# picotouch_synth_flip.net
KiCad netlist of a schematic drawn in EAGLE
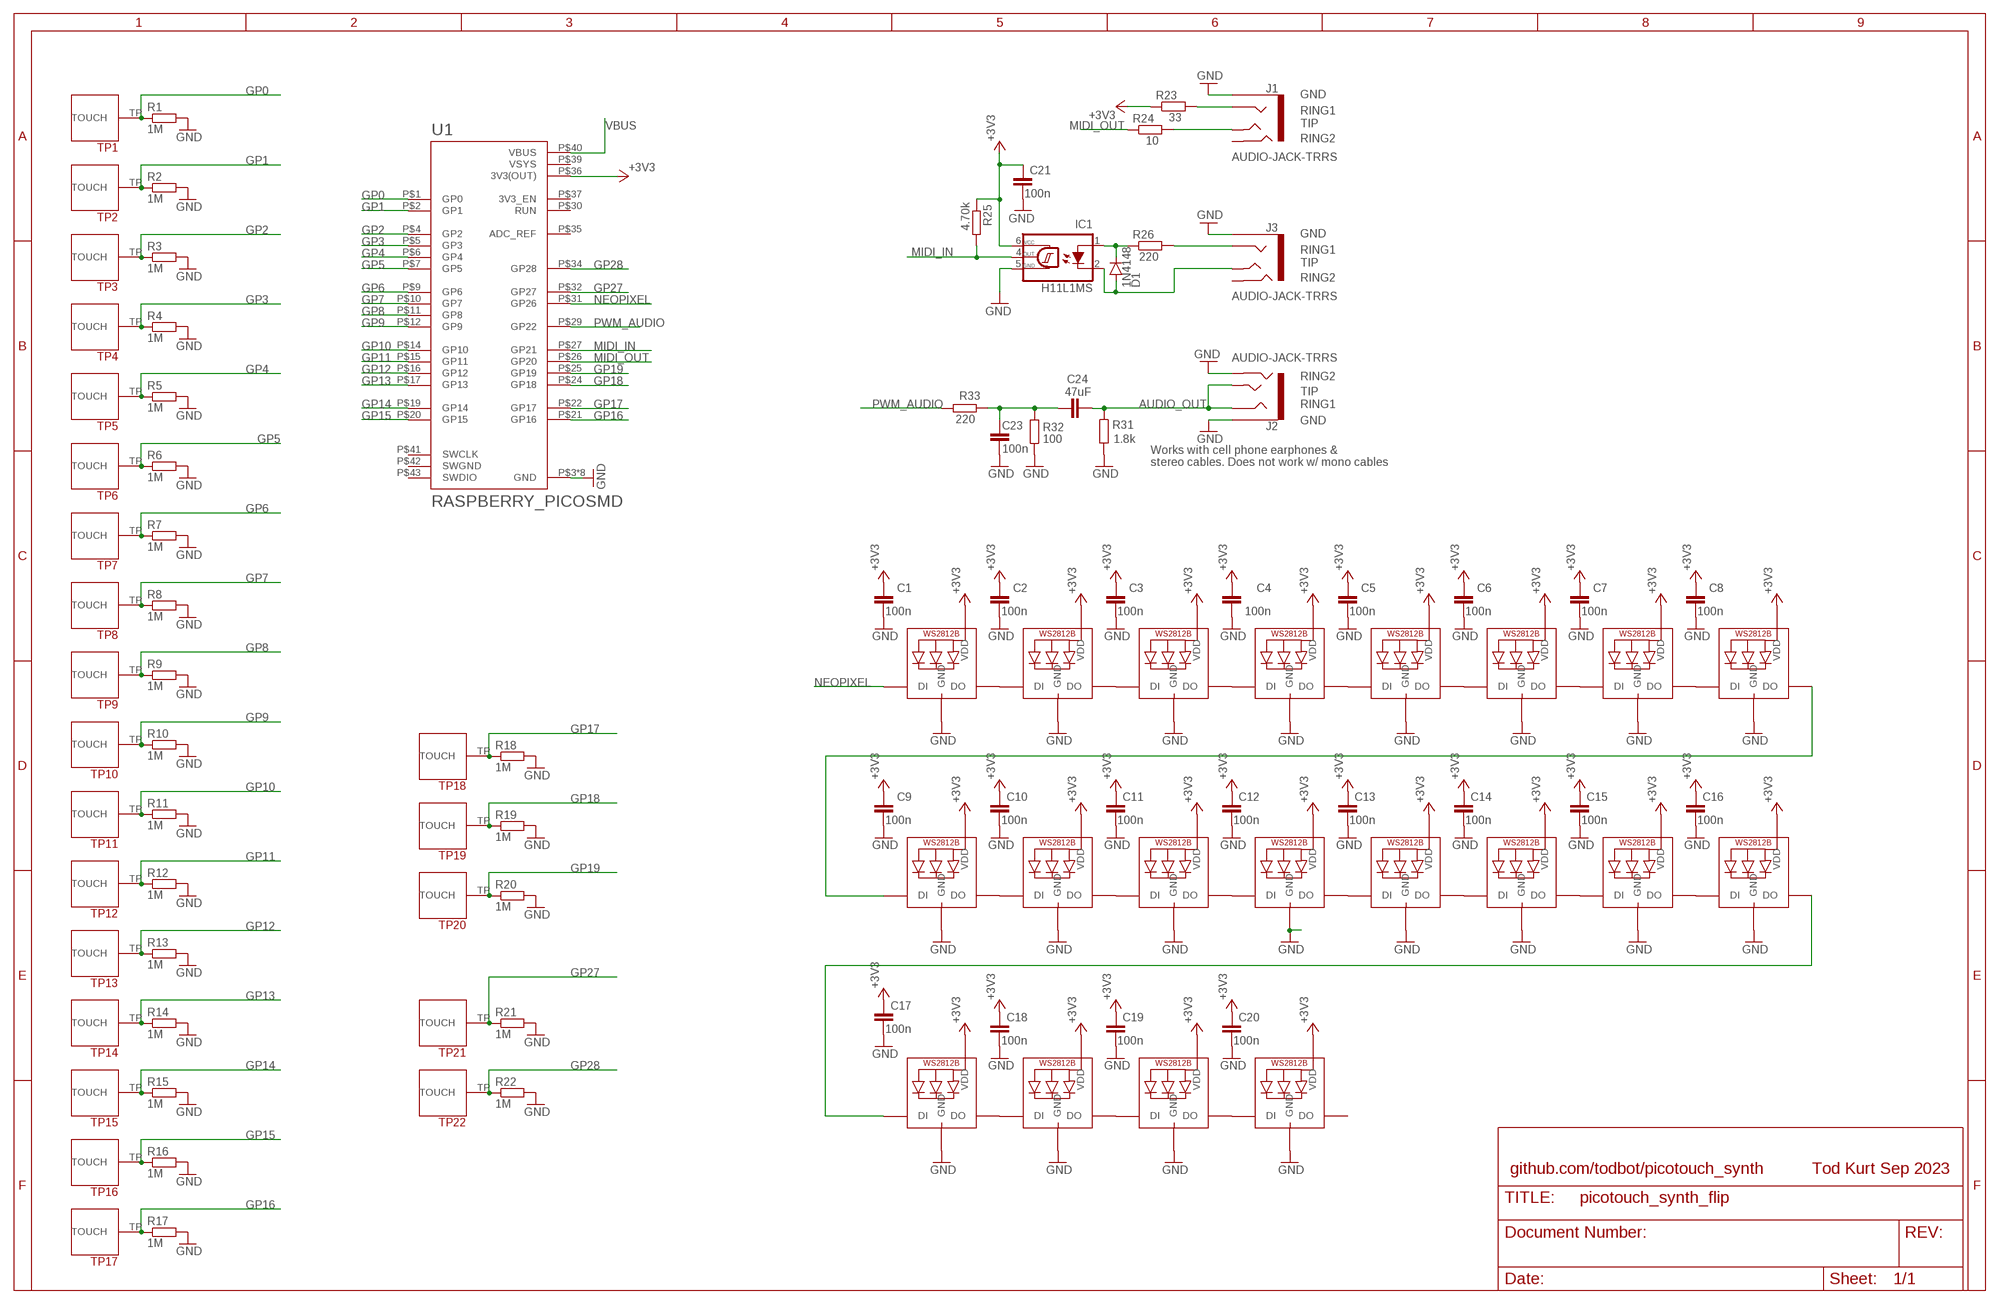
[diagram p0: schematic, sheet 1]

(export (version "E")
  (design (tool "Eeschema 10.0.6"))
  (components
    (comp (ref "C1")
      (value "100n")
      (footprint "eagle-import:C0603")
      (libsource (lib "eagle-import") (part "C-EUC0603"))
    )
    (comp (ref "C2")
      (value "100n")
      (footprint "eagle-import:C0603")
      (libsource (lib "eagle-import") (part "C-EUC0603"))
    )
    (comp (ref "C3")
      (value "100n")
      (footprint "eagle-import:C0603")
      (libsource (lib "eagle-import") (part "C-EUC0603"))
    )
    (comp (ref "C4")
      (value "100n")
      (footprint "eagle-import:C0603")
      (libsource (lib "eagle-import") (part "C-EUC0603"))
    )
    (comp (ref "C5")
      (value "100n")
      (footprint "eagle-import:C0603")
      (libsource (lib "eagle-import") (part "C-EUC0603"))
    )
    (comp (ref "C6")
      (value "100n")
      (footprint "eagle-import:C0603")
      (libsource (lib "eagle-import") (part "C-EUC0603"))
    )
    (comp (ref "C7")
      (value "100n")
      (footprint "eagle-import:C0603")
      (libsource (lib "eagle-import") (part "C-EUC0603"))
    )
    (comp (ref "C8")
      (value "100n")
      (footprint "eagle-import:C0603")
      (libsource (lib "eagle-import") (part "C-EUC0603"))
    )
    (comp (ref "C9")
      (value "100n")
      (footprint "eagle-import:C0603")
      (libsource (lib "eagle-import") (part "C-EUC0603"))
    )
    (comp (ref "C10")
      (value "100n")
      (footprint "eagle-import:C0603")
      (libsource (lib "eagle-import") (part "C-EUC0603"))
    )
    (comp (ref "C11")
      (value "100n")
      (footprint "eagle-import:C0603")
      (libsource (lib "eagle-import") (part "C-EUC0603"))
    )
    (comp (ref "C12")
      (value "100n")
      (footprint "eagle-import:C0603")
      (libsource (lib "eagle-import") (part "C-EUC0603"))
    )
    (comp (ref "C13")
      (value "100n")
      (footprint "eagle-import:C0603")
      (libsource (lib "eagle-import") (part "C-EUC0603"))
    )
    (comp (ref "C14")
      (value "100n")
      (footprint "eagle-import:C0603")
      (libsource (lib "eagle-import") (part "C-EUC0603"))
    )
    (comp (ref "C15")
      (value "100n")
      (footprint "eagle-import:C0603")
      (libsource (lib "eagle-import") (part "C-EUC0603"))
    )
    (comp (ref "C16")
      (value "100n")
      (footprint "eagle-import:C0603")
      (libsource (lib "eagle-import") (part "C-EUC0603"))
    )
    (comp (ref "C17")
      (value "100n")
      (footprint "eagle-import:C0603")
      (libsource (lib "eagle-import") (part "C-EUC0603"))
    )
    (comp (ref "C18")
      (value "100n")
      (footprint "eagle-import:C0603")
      (libsource (lib "eagle-import") (part "C-EUC0603"))
    )
    (comp (ref "C19")
      (value "100n")
      (footprint "eagle-import:C0603")
      (libsource (lib "eagle-import") (part "C-EUC0603"))
    )
    (comp (ref "C20")
      (value "100n")
      (footprint "eagle-import:C0603")
      (libsource (lib "eagle-import") (part "C-EUC0603"))
    )
    (comp (ref "C21")
      (value "100n")
      (footprint "eagle-import:C0603")
      (libsource (lib "eagle-import") (part "C-EUC0603"))
    )
    (comp (ref "C23")
      (value "100n")
      (footprint "eagle-import:C0603")
      (libsource (lib "eagle-import") (part "C-EUC0603"))
    )
    (comp (ref "C24")
      (value "47uF")
      (footprint "eagle-import:C0603")
      (libsource (lib "eagle-import") (part "C-EUC0603"))
    )
    (comp (ref "D1")
      (value "1N4148")
      (footprint "eagle-import:SOD123")
      (libsource (lib "eagle-import") (part "DIODE-SOD123"))
    )
    (comp (ref "IC1")
      (value "H11L1MS")
      (footprint "eagle-import:DIL6-SMD")
      (libsource (lib "eagle-import") (part "H11LMS1"))
    )
    (comp (ref "J1")
      (value "AUDIO-JACK-TRRS")
      (footprint "eagle-import:PJ-320D_SPARKFUN")
      (fields (field (name "MPN") "PJ-320D"))
      (libsource (lib "eagle-import") (part "AUDIO-JACK-TRRS"))
    )
    (comp (ref "J2")
      (value "AUDIO-JACK-TRRS")
      (footprint "eagle-import:PJ-320D_SPARKFUN")
      (fields (field (name "MPN") "PJ-320D") (field (name "LCSC") "C431535"))
      (libsource (lib "eagle-import") (part "AUDIO-JACK-TRRS"))
    )
    (comp (ref "J3")
      (value "AUDIO-JACK-TRRS")
      (footprint "eagle-import:PJ-320D_SPARKFUN")
      (fields (field (name "MPN") "PJ-320D"))
      (libsource (lib "eagle-import") (part "AUDIO-JACK-TRRS"))
    )
    (comp (ref "LED1")
      (value "MICROBUILDER_WS2812B_SK6812E")
      (footprint "eagle-import:MICROBUILDER_NEO3535_REVERSE")
      (libsource (lib "eagle-import") (part "MICROBUILDER_WS2812B_SK6812E"))
    )
    (comp (ref "LED2")
      (value "MICROBUILDER_WS2812B_SK6812E")
      (footprint "eagle-import:MICROBUILDER_NEO3535_REVERSE")
      (libsource (lib "eagle-import") (part "MICROBUILDER_WS2812B_SK6812E"))
    )
    (comp (ref "LED3")
      (value "MICROBUILDER_WS2812B_SK6812E")
      (footprint "eagle-import:MICROBUILDER_NEO3535_REVERSE")
      (libsource (lib "eagle-import") (part "MICROBUILDER_WS2812B_SK6812E"))
    )
    (comp (ref "LED4")
      (value "MICROBUILDER_WS2812B_SK6812E")
      (footprint "eagle-import:MICROBUILDER_NEO3535_REVERSE")
      (libsource (lib "eagle-import") (part "MICROBUILDER_WS2812B_SK6812E"))
    )
    (comp (ref "LED5")
      (value "MICROBUILDER_WS2812B_SK6812E")
      (footprint "eagle-import:MICROBUILDER_NEO3535_REVERSE")
      (libsource (lib "eagle-import") (part "MICROBUILDER_WS2812B_SK6812E"))
    )
    (comp (ref "LED6")
      (value "MICROBUILDER_WS2812B_SK6812E")
      (footprint "eagle-import:MICROBUILDER_NEO3535_REVERSE")
      (libsource (lib "eagle-import") (part "MICROBUILDER_WS2812B_SK6812E"))
    )
    (comp (ref "LED7")
      (value "MICROBUILDER_WS2812B_SK6812E")
      (footprint "eagle-import:MICROBUILDER_NEO3535_REVERSE")
      (libsource (lib "eagle-import") (part "MICROBUILDER_WS2812B_SK6812E"))
    )
    (comp (ref "LED8")
      (value "MICROBUILDER_WS2812B_SK6812E")
      (footprint "eagle-import:MICROBUILDER_NEO3535_REVERSE")
      (libsource (lib "eagle-import") (part "MICROBUILDER_WS2812B_SK6812E"))
    )
    (comp (ref "LED9")
      (value "MICROBUILDER_WS2812B_SK6812E")
      (footprint "eagle-import:MICROBUILDER_NEO3535_REVERSE")
      (libsource (lib "eagle-import") (part "MICROBUILDER_WS2812B_SK6812E"))
    )
    (comp (ref "LED10")
      (value "MICROBUILDER_WS2812B_SK6812E")
      (footprint "eagle-import:MICROBUILDER_NEO3535_REVERSE")
      (libsource (lib "eagle-import") (part "MICROBUILDER_WS2812B_SK6812E"))
    )
    (comp (ref "LED11")
      (value "MICROBUILDER_WS2812B_SK6812E")
      (footprint "eagle-import:MICROBUILDER_NEO3535_REVERSE")
      (libsource (lib "eagle-import") (part "MICROBUILDER_WS2812B_SK6812E"))
    )
    (comp (ref "LED12")
      (value "MICROBUILDER_WS2812B_SK6812E")
      (footprint "eagle-import:MICROBUILDER_NEO3535_REVERSE")
      (libsource (lib "eagle-import") (part "MICROBUILDER_WS2812B_SK6812E"))
    )
    (comp (ref "LED13")
      (value "MICROBUILDER_WS2812B_SK6812E")
      (footprint "eagle-import:MICROBUILDER_NEO3535_REVERSE")
      (libsource (lib "eagle-import") (part "MICROBUILDER_WS2812B_SK6812E"))
    )
    (comp (ref "LED14")
      (value "MICROBUILDER_WS2812B_SK6812E")
      (footprint "eagle-import:MICROBUILDER_NEO3535_REVERSE")
      (libsource (lib "eagle-import") (part "MICROBUILDER_WS2812B_SK6812E"))
    )
    (comp (ref "LED15")
      (value "MICROBUILDER_WS2812B_SK6812E")
      (footprint "eagle-import:MICROBUILDER_NEO3535_REVERSE")
      (libsource (lib "eagle-import") (part "MICROBUILDER_WS2812B_SK6812E"))
    )
    (comp (ref "LED16")
      (value "MICROBUILDER_WS2812B_SK6812E")
      (footprint "eagle-import:MICROBUILDER_NEO3535_REVERSE")
      (libsource (lib "eagle-import") (part "MICROBUILDER_WS2812B_SK6812E"))
    )
    (comp (ref "LED17")
      (value "MICROBUILDER_WS2812B_SK6812E")
      (footprint "eagle-import:MICROBUILDER_NEO3535_REVERSE")
      (libsource (lib "eagle-import") (part "MICROBUILDER_WS2812B_SK6812E"))
    )
    (comp (ref "LED18")
      (value "MICROBUILDER_WS2812B_SK6812E")
      (footprint "eagle-import:MICROBUILDER_NEO3535_REVERSE")
      (libsource (lib "eagle-import") (part "MICROBUILDER_WS2812B_SK6812E"))
    )
    (comp (ref "LED19")
      (value "MICROBUILDER_WS2812B_SK6812E")
      (footprint "eagle-import:MICROBUILDER_NEO3535_REVERSE")
      (libsource (lib "eagle-import") (part "MICROBUILDER_WS2812B_SK6812E"))
    )
    (comp (ref "LED20")
      (value "MICROBUILDER_WS2812B_SK6812E")
      (footprint "eagle-import:MICROBUILDER_NEO3535_REVERSE")
      (libsource (lib "eagle-import") (part "MICROBUILDER_WS2812B_SK6812E"))
    )
    (comp (ref "R1")
      (value "1M")
      (footprint "eagle-import:R0805")
      (libsource (lib "eagle-import") (part "R-EU_R0805"))
    )
    (comp (ref "R2")
      (value "1M")
      (footprint "eagle-import:R0805")
      (libsource (lib "eagle-import") (part "R-EU_R0805"))
    )
    (comp (ref "R3")
      (value "1M")
      (footprint "eagle-import:R0805")
      (libsource (lib "eagle-import") (part "R-EU_R0805"))
    )
    (comp (ref "R4")
      (value "1M")
      (footprint "eagle-import:R0805")
      (libsource (lib "eagle-import") (part "R-EU_R0805"))
    )
    (comp (ref "R5")
      (value "1M")
      (footprint "eagle-import:R0805")
      (libsource (lib "eagle-import") (part "R-EU_R0805"))
    )
    (comp (ref "R6")
      (value "1M")
      (footprint "eagle-import:R0805")
      (libsource (lib "eagle-import") (part "R-EU_R0805"))
    )
    (comp (ref "R7")
      (value "1M")
      (footprint "eagle-import:R0805")
      (libsource (lib "eagle-import") (part "R-EU_R0805"))
    )
    (comp (ref "R8")
      (value "1M")
      (footprint "eagle-import:R0805")
      (libsource (lib "eagle-import") (part "R-EU_R0805"))
    )
    (comp (ref "R9")
      (value "1M")
      (footprint "eagle-import:R0805")
      (libsource (lib "eagle-import") (part "R-EU_R0805"))
    )
    (comp (ref "R10")
      (value "1M")
      (footprint "eagle-import:R0805")
      (libsource (lib "eagle-import") (part "R-EU_R0805"))
    )
    (comp (ref "R11")
      (value "1M")
      (footprint "eagle-import:R0805")
      (libsource (lib "eagle-import") (part "R-EU_R0805"))
    )
    (comp (ref "R12")
      (value "1M")
      (footprint "eagle-import:R0805")
      (libsource (lib "eagle-import") (part "R-EU_R0805"))
    )
    (comp (ref "R13")
      (value "1M")
      (footprint "eagle-import:R0805")
      (libsource (lib "eagle-import") (part "R-EU_R0805"))
    )
    (comp (ref "R14")
      (value "1M")
      (footprint "eagle-import:R0805")
      (libsource (lib "eagle-import") (part "R-EU_R0805"))
    )
    (comp (ref "R15")
      (value "1M")
      (footprint "eagle-import:R0805")
      (libsource (lib "eagle-import") (part "R-EU_R0805"))
    )
    (comp (ref "R16")
      (value "1M")
      (footprint "eagle-import:R0805")
      (libsource (lib "eagle-import") (part "R-EU_R0805"))
    )
    (comp (ref "R17")
      (value "1M")
      (footprint "eagle-import:R0805")
      (libsource (lib "eagle-import") (part "R-EU_R0805"))
    )
    (comp (ref "R18")
      (value "1M")
      (footprint "eagle-import:R0603")
      (libsource (lib "eagle-import") (part "R-EU_R0603"))
    )
    (comp (ref "R19")
      (value "1M")
      (footprint "eagle-import:R0603")
      (libsource (lib "eagle-import") (part "R-EU_R0603"))
    )
    (comp (ref "R20")
      (value "1M")
      (footprint "eagle-import:R0603")
      (libsource (lib "eagle-import") (part "R-EU_R0603"))
    )
    (comp (ref "R21")
      (value "1M")
      (footprint "eagle-import:R0603")
      (libsource (lib "eagle-import") (part "R-EU_R0603"))
    )
    (comp (ref "R22")
      (value "1M")
      (footprint "eagle-import:R0603")
      (libsource (lib "eagle-import") (part "R-EU_R0603"))
    )
    (comp (ref "R23")
      (value "33")
      (footprint "eagle-import:R0603")
      (libsource (lib "eagle-import") (part "R-EU_R0603"))
    )
    (comp (ref "R24")
      (value "10")
      (footprint "eagle-import:R0603")
      (libsource (lib "eagle-import") (part "R-EU_R0603"))
    )
    (comp (ref "R25")
      (value "4.70k")
      (footprint "eagle-import:R0603")
      (libsource (lib "eagle-import") (part "R-EU_R0603"))
    )
    (comp (ref "R26")
      (value "220")
      (footprint "eagle-import:R0603")
      (libsource (lib "eagle-import") (part "R-EU_R0603"))
    )
    (comp (ref "R31")
      (value "1.8k")
      (footprint "eagle-import:R0603")
      (libsource (lib "eagle-import") (part "R-EU_R0603"))
    )
    (comp (ref "R32")
      (value "100")
      (footprint "eagle-import:R0603")
      (libsource (lib "eagle-import") (part "R-EU_R0603"))
    )
    (comp (ref "R33")
      (value "220")
      (footprint "eagle-import:R0603")
      (libsource (lib "eagle-import") (part "R-EU_R0603"))
    )
    (comp (ref "TP1")
      (value "TOUCHPADA")
      (footprint "eagle-import:TOUCHPADA")
      (libsource (lib "eagle-import") (part "TOUCHPADA"))
    )
    (comp (ref "TP2")
      (value "TOUCHPADA")
      (footprint "eagle-import:TOUCHPADA")
      (libsource (lib "eagle-import") (part "TOUCHPADA"))
    )
    (comp (ref "TP3")
      (value "TOUCHPADA")
      (footprint "eagle-import:TOUCHPADA")
      (libsource (lib "eagle-import") (part "TOUCHPADA"))
    )
    (comp (ref "TP4")
      (value "TOUCHPADA")
      (footprint "eagle-import:TOUCHPADA")
      (libsource (lib "eagle-import") (part "TOUCHPADA"))
    )
    (comp (ref "TP5")
      (value "TOUCHPADA")
      (footprint "eagle-import:TOUCHPADA")
      (libsource (lib "eagle-import") (part "TOUCHPADA"))
    )
    (comp (ref "TP6")
      (value "TOUCHPADA")
      (footprint "eagle-import:TOUCHPADA")
      (libsource (lib "eagle-import") (part "TOUCHPADA"))
    )
    (comp (ref "TP7")
      (value "TOUCHPADA")
      (footprint "eagle-import:TOUCHPADA")
      (libsource (lib "eagle-import") (part "TOUCHPADA"))
    )
    (comp (ref "TP8")
      (value "TOUCHPADA")
      (footprint "eagle-import:TOUCHPADA")
      (libsource (lib "eagle-import") (part "TOUCHPADA"))
    )
    (comp (ref "TP9")
      (value "TOUCHPADA")
      (footprint "eagle-import:TOUCHPADA")
      (libsource (lib "eagle-import") (part "TOUCHPADA"))
    )
    (comp (ref "TP10")
      (value "TOUCHPADA")
      (footprint "eagle-import:TOUCHPADA")
      (libsource (lib "eagle-import") (part "TOUCHPADA"))
    )
    (comp (ref "TP11")
      (value "TOUCHPADA")
      (footprint "eagle-import:TOUCHPADA")
      (libsource (lib "eagle-import") (part "TOUCHPADA"))
    )
    (comp (ref "TP12")
      (value "TOUCHPADA")
      (footprint "eagle-import:TOUCHPADA")
      (libsource (lib "eagle-import") (part "TOUCHPADA"))
    )
    (comp (ref "TP13")
      (value "TOUCHPADA")
      (footprint "eagle-import:TOUCHPADA")
      (libsource (lib "eagle-import") (part "TOUCHPADA"))
    )
    (comp (ref "TP14")
      (value "TOUCHPADA")
      (footprint "eagle-import:TOUCHPADA")
      (libsource (lib "eagle-import") (part "TOUCHPADA"))
    )
    (comp (ref "TP15")
      (value "TOUCHPADA")
      (footprint "eagle-import:TOUCHPADA")
      (libsource (lib "eagle-import") (part "TOUCHPADA"))
    )
    (comp (ref "TP16")
      (value "TOUCHPADA")
      (footprint "eagle-import:TOUCHPADA")
      (libsource (lib "eagle-import") (part "TOUCHPADA"))
    )
    (comp (ref "TP17")
      (value "TOUCHPADA")
      (footprint "eagle-import:TOUCHPADA")
      (libsource (lib "eagle-import") (part "TOUCHPADA"))
    )
    (comp (ref "TP18")
      (value "TOUCHPADB")
      (footprint "eagle-import:TOUCHPADB")
      (libsource (lib "eagle-import") (part "TOUCHPADB"))
    )
    (comp (ref "TP19")
      (value "TOUCHPADB")
      (footprint "eagle-import:TOUCHPADB")
      (libsource (lib "eagle-import") (part "TOUCHPADB"))
    )
    (comp (ref "TP20")
      (value "TOUCHPADB")
      (footprint "eagle-import:TOUCHPADB")
      (libsource (lib "eagle-import") (part "TOUCHPADB"))
    )
    (comp (ref "TP21")
      (value "TOUCHPADB")
      (footprint "eagle-import:TOUCHPADB")
      (libsource (lib "eagle-import") (part "TOUCHPADB"))
    )
    (comp (ref "TP22")
      (value "TOUCHPADB")
      (footprint "eagle-import:TOUCHPADB")
      (libsource (lib "eagle-import") (part "TOUCHPADB"))
    )
    (comp (ref "U1")
      (value "RASPBERRY_PICOSMD")
      (footprint "eagle-import:PICO-PKG-SMD")
      (libsource (lib "eagle-import") (part "RASPBERRY_PICOSMD"))
    )
  )
  (nets
    (net (code "1") (name "+3V3") (class "Default")
      (node (ref "C1") (pin "1") (pinfunction "1_1") (pintype "passive"))
      (node (ref "C10") (pin "1") (pinfunction "1_1") (pintype "passive"))
      (node (ref "C11") (pin "1") (pinfunction "1_1") (pintype "passive"))
      (node (ref "C12") (pin "1") (pinfunction "1_1") (pintype "passive"))
      (node (ref "C13") (pin "1") (pinfunction "1_1") (pintype "passive"))
      (node (ref "C14") (pin "1") (pinfunction "1_1") (pintype "passive"))
      (node (ref "C15") (pin "1") (pinfunction "1_1") (pintype "passive"))
      (node (ref "C16") (pin "1") (pinfunction "1_1") (pintype "passive"))
      (node (ref "C17") (pin "1") (pinfunction "1_1") (pintype "passive"))
      (node (ref "C18") (pin "1") (pinfunction "1_1") (pintype "passive"))
      (node (ref "C19") (pin "1") (pinfunction "1_1") (pintype "passive"))
      (node (ref "C2") (pin "1") (pinfunction "1_1") (pintype "passive"))
      (node (ref "C20") (pin "1") (pinfunction "1_1") (pintype "passive"))
      (node (ref "C21") (pin "1") (pinfunction "1_1") (pintype "passive"))
      (node (ref "C3") (pin "1") (pinfunction "1_1") (pintype "passive"))
      (node (ref "C4") (pin "1") (pinfunction "1_1") (pintype "passive"))
      (node (ref "C5") (pin "1") (pinfunction "1_1") (pintype "passive"))
      (node (ref "C6") (pin "1") (pinfunction "1_1") (pintype "passive"))
      (node (ref "C7") (pin "1") (pinfunction "1_1") (pintype "passive"))
      (node (ref "C8") (pin "1") (pinfunction "1_1") (pintype "passive"))
      (node (ref "C9") (pin "1") (pinfunction "1_1") (pintype "passive"))
      (node (ref "IC1") (pin "6") (pinfunction "VCC_6") (pintype "power_in"))
      (node (ref "LED1") (pin "1-VDD") (pinfunction "VDD_1-VDD") (pintype "power_in"))
      (node (ref "LED10") (pin "1-VDD") (pinfunction "VDD_1-VDD") (pintype "power_in"))
      (node (ref "LED11") (pin "1-VDD") (pinfunction "VDD_1-VDD") (pintype "power_in"))
      (node (ref "LED12") (pin "1-VDD") (pinfunction "VDD_1-VDD") (pintype "power_in"))
      (node (ref "LED13") (pin "1-VDD") (pinfunction "VDD_1-VDD") (pintype "power_in"))
      (node (ref "LED14") (pin "1-VDD") (pinfunction "VDD_1-VDD") (pintype "power_in"))
      (node (ref "LED15") (pin "1-VDD") (pinfunction "VDD_1-VDD") (pintype "power_in"))
      (node (ref "LED16") (pin "1-VDD") (pinfunction "VDD_1-VDD") (pintype "power_in"))
      (node (ref "LED17") (pin "1-VDD") (pinfunction "VDD_1-VDD") (pintype "power_in"))
      (node (ref "LED18") (pin "1-VDD") (pinfunction "VDD_1-VDD") (pintype "power_in"))
      (node (ref "LED19") (pin "1-VDD") (pinfunction "VDD_1-VDD") (pintype "power_in"))
      (node (ref "LED2") (pin "1-VDD") (pinfunction "VDD_1-VDD") (pintype "power_in"))
      (node (ref "LED20") (pin "1-VDD") (pinfunction "VDD_1-VDD") (pintype "power_in"))
      (node (ref "LED3") (pin "1-VDD") (pinfunction "VDD_1-VDD") (pintype "power_in"))
      (node (ref "LED4") (pin "1-VDD") (pinfunction "VDD_1-VDD") (pintype "power_in"))
      (node (ref "LED5") (pin "1-VDD") (pinfunction "VDD_1-VDD") (pintype "power_in"))
      (node (ref "LED6") (pin "1-VDD") (pinfunction "VDD_1-VDD") (pintype "power_in"))
      (node (ref "LED7") (pin "1-VDD") (pinfunction "VDD_1-VDD") (pintype "power_in"))
      (node (ref "LED8") (pin "1-VDD") (pinfunction "VDD_1-VDD") (pintype "power_in"))
      (node (ref "LED9") (pin "1-VDD") (pinfunction "VDD_1-VDD") (pintype "power_in"))
      (node (ref "R23") (pin "1") (pinfunction "1_1") (pintype "passive"))
      (node (ref "R25") (pin "1") (pinfunction "1_1") (pintype "passive"))
      (node (ref "U1") (pin "P$36") (pinfunction "3V3(OUT)_P$36") (pintype "power_in"))
    )
    (net (code "2") (name "/AUDIO_OUT") (class "Default")
      (node (ref "C24") (pin "2") (pinfunction "2_2") (pintype "passive"))
      (node (ref "J2") (pin "RING1") (pinfunction "RING1_RING1") (pintype "bidirectional"))
      (node (ref "J2") (pin "TIP") (pinfunction "TIP_TIP") (pintype "bidirectional"))
      (node (ref "R31") (pin "1") (pinfunction "1_1") (pintype "passive"))
    )
    (net (code "3") (name "/GP0") (class "Default")
      (node (ref "R1") (pin "1") (pinfunction "1_1") (pintype "passive"))
      (node (ref "TP1") (pin "TP") (pinfunction "TOUCH_TP") (pintype "bidirectional"))
      (node (ref "U1") (pin "P$1") (pinfunction "GP0_P$1") (pintype "bidirectional"))
    )
    (net (code "4") (name "/GP1") (class "Default")
      (node (ref "R2") (pin "1") (pinfunction "1_1") (pintype "passive"))
      (node (ref "TP2") (pin "TP") (pinfunction "TOUCH_TP") (pintype "bidirectional"))
      (node (ref "U1") (pin "P$2") (pinfunction "GP1_P$2") (pintype "bidirectional"))
    )
    (net (code "5") (name "/GP2") (class "Default")
      (node (ref "R3") (pin "1") (pinfunction "1_1") (pintype "passive"))
      (node (ref "TP3") (pin "TP") (pinfunction "TOUCH_TP") (pintype "bidirectional"))
      (node (ref "U1") (pin "P$4") (pinfunction "GP2_P$4") (pintype "bidirectional"))
    )
    (net (code "6") (name "/GP3") (class "Default")
      (node (ref "R4") (pin "1") (pinfunction "1_1") (pintype "passive"))
      (node (ref "TP4") (pin "TP") (pinfunction "TOUCH_TP") (pintype "bidirectional"))
      (node (ref "U1") (pin "P$5") (pinfunction "GP3_P$5") (pintype "bidirectional"))
    )
    (net (code "7") (name "/GP4") (class "Default")
      (node (ref "R5") (pin "1") (pinfunction "1_1") (pintype "passive"))
      (node (ref "TP5") (pin "TP") (pinfunction "TOUCH_TP") (pintype "bidirectional"))
      (node (ref "U1") (pin "P$6") (pinfunction "GP4_P$6") (pintype "bidirectional"))
    )
    (net (code "8") (name "/GP5") (class "Default")
      (node (ref "R6") (pin "1") (pinfunction "1_1") (pintype "passive"))
      (node (ref "TP6") (pin "TP") (pinfunction "TOUCH_TP") (pintype "bidirectional"))
      (node (ref "U1") (pin "P$7") (pinfunction "GP5_P$7") (pintype "bidirectional"))
    )
    (net (code "9") (name "/GP6") (class "Default")
      (node (ref "R7") (pin "1") (pinfunction "1_1") (pintype "passive"))
      (node (ref "TP7") (pin "TP") (pinfunction "TOUCH_TP") (pintype "bidirectional"))
      (node (ref "U1") (pin "P$9") (pinfunction "GP6_P$9") (pintype "bidirectional"))
    )
    (net (code "10") (name "/GP7") (class "Default")
      (node (ref "R8") (pin "1") (pinfunction "1_1") (pintype "passive"))
      (node (ref "TP8") (pin "TP") (pinfunction "TOUCH_TP") (pintype "bidirectional"))
      (node (ref "U1") (pin "P$10") (pinfunction "GP7_P$10") (pintype "bidirectional"))
    )
    (net (code "11") (name "/GP8") (class "Default")
      (node (ref "R9") (pin "1") (pinfunction "1_1") (pintype "passive"))
      (node (ref "TP9") (pin "TP") (pinfunction "TOUCH_TP") (pintype "bidirectional"))
      (node (ref "U1") (pin "P$11") (pinfunction "GP8_P$11") (pintype "bidirectional"))
    )
    (net (code "12") (name "/GP9") (class "Default")
      (node (ref "R10") (pin "1") (pinfunction "1_1") (pintype "passive"))
      (node (ref "TP10") (pin "TP") (pinfunction "TOUCH_TP") (pintype "bidirectional"))
      (node (ref "U1") (pin "P$12") (pinfunction "GP9_P$12") (pintype "bidirectional"))
    )
    (net (code "13") (name "/GP10") (class "Default")
      (node (ref "R11") (pin "1") (pinfunction "1_1") (pintype "passive"))
      (node (ref "TP11") (pin "TP") (pinfunction "TOUCH_TP") (pintype "bidirectional"))
      (node (ref "U1") (pin "P$14") (pinfunction "GP10_P$14") (pintype "bidirectional"))
    )
    (net (code "14") (name "/GP11") (class "Default")
      (node (ref "R12") (pin "1") (pinfunction "1_1") (pintype "passive"))
      (node (ref "TP12") (pin "TP") (pinfunction "TOUCH_TP") (pintype "bidirectional"))
      (node (ref "U1") (pin "P$15") (pinfunction "GP11_P$15") (pintype "bidirectional"))
    )
    (net (code "15") (name "/GP12") (class "Default")
      (node (ref "R13") (pin "1") (pinfunction "1_1") (pintype "passive"))
      (node (ref "TP13") (pin "TP") (pinfunction "TOUCH_TP") (pintype "bidirectional"))
      (node (ref "U1") (pin "P$16") (pinfunction "GP12_P$16") (pintype "bidirectional"))
    )
    (net (code "16") (name "/GP13") (class "Default")
      (node (ref "R14") (pin "1") (pinfunction "1_1") (pintype "passive"))
      (node (ref "TP14") (pin "TP") (pinfunction "TOUCH_TP") (pintype "bidirectional"))
      (node (ref "U1") (pin "P$17") (pinfunction "GP13_P$17") (pintype "bidirectional"))
    )
    (net (code "17") (name "/GP14") (class "Default")
      (node (ref "R15") (pin "1") (pinfunction "1_1") (pintype "passive"))
      (node (ref "TP15") (pin "TP") (pinfunction "TOUCH_TP") (pintype "bidirectional"))
      (node (ref "U1") (pin "P$19") (pinfunction "GP14_P$19") (pintype "bidirectional"))
    )
    (net (code "18") (name "/GP15") (class "Default")
      (node (ref "R16") (pin "1") (pinfunction "1_1") (pintype "passive"))
      (node (ref "TP16") (pin "TP") (pinfunction "TOUCH_TP") (pintype "bidirectional"))
      (node (ref "U1") (pin "P$20") (pinfunction "GP15_P$20") (pintype "bidirectional"))
    )
    (net (code "19") (name "/GP16") (class "Default")
      (node (ref "R17") (pin "1") (pinfunction "1_1") (pintype "passive"))
      (node (ref "TP17") (pin "TP") (pinfunction "TOUCH_TP") (pintype "bidirectional"))
      (node (ref "U1") (pin "P$21") (pinfunction "GP16_P$21") (pintype "bidirectional"))
    )
    (net (code "20") (name "/GP17") (class "Default")
      (node (ref "R18") (pin "1") (pinfunction "1_1") (pintype "passive"))
      (node (ref "TP18") (pin "TP") (pinfunction "TOUCH_TP") (pintype "bidirectional"))
      (node (ref "U1") (pin "P$22") (pinfunction "GP17_P$22") (pintype "bidirectional"))
    )
    (net (code "21") (name "/GP18") (class "Default")
      (node (ref "R19") (pin "1") (pinfunction "1_1") (pintype "passive"))
      (node (ref "TP19") (pin "TP") (pinfunction "TOUCH_TP") (pintype "bidirectional"))
      (node (ref "U1") (pin "P$24") (pinfunction "GP18_P$24") (pintype "bidirectional"))
    )
    (net (code "22") (name "/GP19") (class "Default")
      (node (ref "R20") (pin "1") (pinfunction "1_1") (pintype "passive"))
      (node (ref "TP20") (pin "TP") (pinfunction "TOUCH_TP") (pintype "bidirectional"))
      (node (ref "U1") (pin "P$25") (pinfunction "GP19_P$25") (pintype "bidirectional"))
    )
    (net (code "23") (name "/GP27") (class "Default")
      (node (ref "R21") (pin "1") (pinfunction "1_1") (pintype "passive"))
      (node (ref "TP21") (pin "TP") (pinfunction "TOUCH_TP") (pintype "bidirectional"))
      (node (ref "U1") (pin "P$32") (pinfunction "GP27_P$32") (pintype "bidirectional"))
    )
    (net (code "24") (name "/GP28") (class "Default")
      (node (ref "R22") (pin "1") (pinfunction "1_1") (pintype "passive"))
      (node (ref "TP22") (pin "TP") (pinfunction "TOUCH_TP") (pintype "bidirectional"))
      (node (ref "U1") (pin "P$34") (pinfunction "GP28_P$34") (pintype "bidirectional"))
    )
    (net (code "25") (name "/MIDI_IN") (class "Default")
      (node (ref "IC1") (pin "4") (pinfunction "OUT_4") (pintype "output"))
      (node (ref "R25") (pin "2") (pinfunction "2_2") (pintype "passive"))
      (node (ref "U1") (pin "P$27") (pinfunction "GP21_P$27") (pintype "bidirectional"))
    )
    (net (code "26") (name "/MIDI_OUT") (class "Default")
      (node (ref "R24") (pin "1") (pinfunction "1_1") (pintype "passive"))
      (node (ref "U1") (pin "P$26") (pinfunction "GP20_P$26") (pintype "bidirectional"))
    )
    (net (code "27") (name "/NEOPIXEL") (class "Default")
      (node (ref "LED1") (pin "4-DIN") (pinfunction "DI_4-DIN") (pintype "input"))
      (node (ref "U1") (pin "P$31") (pinfunction "GP26_P$31") (pintype "bidirectional"))
    )
    (net (code "28") (name "/PWM_AUDIO") (class "Default")
      (node (ref "R33") (pin "2") (pinfunction "2_2") (pintype "passive"))
      (node (ref "U1") (pin "P$29") (pinfunction "GP22_P$29") (pintype "bidirectional"))
    )
    (net (code "29") (name "/SWGND") (class "Default")
      (node (ref "U1") (pin "P$42") (pinfunction "SWGND_P$42") (pintype "power_in"))
    )
    (net (code "30") (name "/VBUS") (class "Default")
      (node (ref "U1") (pin "P$40") (pinfunction "VBUS_P$40") (pintype "power_in"))
    )
    (net (code "31") (name "/VSYS") (class "Default")
      (node (ref "U1") (pin "P$39") (pinfunction "VSYS_P$39") (pintype "power_in"))
    )
    (net (code "32") (name "GND") (class "Default")
      (node (ref "C1") (pin "2") (pinfunction "2_2") (pintype "passive"))
      (node (ref "C10") (pin "2") (pinfunction "2_2") (pintype "passive"))
      (node (ref "C11") (pin "2") (pinfunction "2_2") (pintype "passive"))
      (node (ref "C12") (pin "2") (pinfunction "2_2") (pintype "passive"))
      (node (ref "C13") (pin "2") (pinfunction "2_2") (pintype "passive"))
      (node (ref "C14") (pin "2") (pinfunction "2_2") (pintype "passive"))
      (node (ref "C15") (pin "2") (pinfunction "2_2") (pintype "passive"))
      (node (ref "C16") (pin "2") (pinfunction "2_2") (pintype "passive"))
      (node (ref "C17") (pin "2") (pinfunction "2_2") (pintype "passive"))
      (node (ref "C18") (pin "2") (pinfunction "2_2") (pintype "passive"))
      (node (ref "C19") (pin "2") (pinfunction "2_2") (pintype "passive"))
      (node (ref "C2") (pin "2") (pinfunction "2_2") (pintype "passive"))
      (node (ref "C20") (pin "2") (pinfunction "2_2") (pintype "passive"))
      (node (ref "C21") (pin "2") (pinfunction "2_2") (pintype "passive"))
      (node (ref "C23") (pin "2") (pinfunction "2_2") (pintype "passive"))
      (node (ref "C3") (pin "2") (pinfunction "2_2") (pintype "passive"))
      (node (ref "C4") (pin "2") (pinfunction "2_2") (pintype "passive"))
      (node (ref "C5") (pin "2") (pinfunction "2_2") (pintype "passive"))
      (node (ref "C6") (pin "2") (pinfunction "2_2") (pintype "passive"))
      (node (ref "C7") (pin "2") (pinfunction "2_2") (pintype "passive"))
      (node (ref "C8") (pin "2") (pinfunction "2_2") (pintype "passive"))
      (node (ref "C9") (pin "2") (pinfunction "2_2") (pintype "passive"))
      (node (ref "IC1") (pin "5") (pinfunction "GND_5") (pintype "power_in"))
      (node (ref "J1") (pin "EARTH") (pinfunction "EARTH_EARTH") (pintype "bidirectional"))
      (node (ref "J2") (pin "EARTH") (pinfunction "EARTH_EARTH") (pintype "bidirectional"))
      (node (ref "J2") (pin "RING2") (pinfunction "RING2_RING2") (pintype "bidirectional"))
      (node (ref "J3") (pin "EARTH") (pinfunction "EARTH_EARTH") (pintype "bidirectional"))
      (node (ref "LED1") (pin "3-GND") (pinfunction "GND_3-GND") (pintype "power_in"))
      (node (ref "LED10") (pin "3-GND") (pinfunction "GND_3-GND") (pintype "power_in"))
      (node (ref "LED11") (pin "3-GND") (pinfunction "GND_3-GND") (pintype "power_in"))
      (node (ref "LED12") (pin "3-GND") (pinfunction "GND_3-GND") (pintype "power_in"))
      (node (ref "LED13") (pin "3-GND") (pinfunction "GND_3-GND") (pintype "power_in"))
      (node (ref "LED14") (pin "3-GND") (pinfunction "GND_3-GND") (pintype "power_in"))
      (node (ref "LED15") (pin "3-GND") (pinfunction "GND_3-GND") (pintype "power_in"))
      (node (ref "LED16") (pin "3-GND") (pinfunction "GND_3-GND") (pintype "power_in"))
      (node (ref "LED17") (pin "3-GND") (pinfunction "GND_3-GND") (pintype "power_in"))
      (node (ref "LED18") (pin "3-GND") (pinfunction "GND_3-GND") (pintype "power_in"))
      (node (ref "LED19") (pin "3-GND") (pinfunction "GND_3-GND") (pintype "power_in"))
      (node (ref "LED2") (pin "3-GND") (pinfunction "GND_3-GND") (pintype "power_in"))
      (node (ref "LED20") (pin "3-GND") (pinfunction "GND_3-GND") (pintype "power_in"))
      (node (ref "LED3") (pin "3-GND") (pinfunction "GND_3-GND") (pintype "power_in"))
      (node (ref "LED4") (pin "3-GND") (pinfunction "GND_3-GND") (pintype "power_in"))
      (node (ref "LED5") (pin "3-GND") (pinfunction "GND_3-GND") (pintype "power_in"))
      (node (ref "LED6") (pin "3-GND") (pinfunction "GND_3-GND") (pintype "power_in"))
      (node (ref "LED7") (pin "3-GND") (pinfunction "GND_3-GND") (pintype "power_in"))
      (node (ref "LED8") (pin "3-GND") (pinfunction "GND_3-GND") (pintype "power_in"))
      (node (ref "LED9") (pin "3-GND") (pinfunction "GND_3-GND") (pintype "power_in"))
      (node (ref "R1") (pin "2") (pinfunction "2_2") (pintype "passive"))
      (node (ref "R10") (pin "2") (pinfunction "2_2") (pintype "passive"))
      (node (ref "R11") (pin "2") (pinfunction "2_2") (pintype "passive"))
      (node (ref "R12") (pin "2") (pinfunction "2_2") (pintype "passive"))
      (node (ref "R13") (pin "2") (pinfunction "2_2") (pintype "passive"))
      (node (ref "R14") (pin "2") (pinfunction "2_2") (pintype "passive"))
      (node (ref "R15") (pin "2") (pinfunction "2_2") (pintype "passive"))
      (node (ref "R16") (pin "2") (pinfunction "2_2") (pintype "passive"))
      (node (ref "R17") (pin "2") (pinfunction "2_2") (pintype "passive"))
      (node (ref "R18") (pin "2") (pinfunction "2_2") (pintype "passive"))
      (node (ref "R19") (pin "2") (pinfunction "2_2") (pintype "passive"))
      (node (ref "R2") (pin "2") (pinfunction "2_2") (pintype "passive"))
      (node (ref "R20") (pin "2") (pinfunction "2_2") (pintype "passive"))
      (node (ref "R21") (pin "2") (pinfunction "2_2") (pintype "passive"))
      (node (ref "R22") (pin "2") (pinfunction "2_2") (pintype "passive"))
      (node (ref "R3") (pin "2") (pinfunction "2_2") (pintype "passive"))
      (node (ref "R31") (pin "2") (pinfunction "2_2") (pintype "passive"))
      (node (ref "R32") (pin "1") (pinfunction "1_1") (pintype "passive"))
      (node (ref "R4") (pin "2") (pinfunction "2_2") (pintype "passive"))
      (node (ref "R5") (pin "2") (pinfunction "2_2") (pintype "passive"))
      (node (ref "R6") (pin "2") (pinfunction "2_2") (pintype "passive"))
      (node (ref "R7") (pin "2") (pinfunction "2_2") (pintype "passive"))
      (node (ref "R8") (pin "2") (pinfunction "2_2") (pintype "passive"))
      (node (ref "R9") (pin "2") (pinfunction "2_2") (pintype "passive"))
      (node (ref "U1") (pin "P$13") (pinfunction "GND_P$13") (pintype "power_in"))
      (node (ref "U1") (pin "P$18") (pinfunction "GND_P$18") (pintype "power_in"))
      (node (ref "U1") (pin "P$23") (pinfunction "GND_P$23") (pintype "power_in"))
      (node (ref "U1") (pin "P$28") (pinfunction "GND_P$28") (pintype "power_in"))
      (node (ref "U1") (pin "P$3") (pinfunction "GND_P$3") (pintype "power_in"))
      (node (ref "U1") (pin "P$33") (pinfunction "GND_P$33") (pintype "power_in"))
      (node (ref "U1") (pin "P$38") (pinfunction "GND_P$38") (pintype "power_in"))
      (node (ref "U1") (pin "P$8") (pinfunction "GND_P$8") (pintype "power_in"))
    )
    (net (code "33") (name "Net-(C23-Pad1)") (class "Default")
      (node (ref "C23") (pin "1") (pinfunction "1_1") (pintype "passive"))
      (node (ref "C24") (pin "1") (pinfunction "1_1") (pintype "passive"))
      (node (ref "R32") (pin "2") (pinfunction "2_2") (pintype "passive"))
      (node (ref "R33") (pin "1") (pinfunction "1_1") (pintype "passive"))
    )
    (net (code "34") (name "Net-(IC1-A)") (class "Default")
      (node (ref "D1") (pin "C") (pinfunction "C_C") (pintype "passive"))
      (node (ref "IC1") (pin "1") (pinfunction "A_1") (pintype "passive"))
      (node (ref "R26") (pin "1") (pinfunction "1_1") (pintype "passive"))
    )
    (net (code "35") (name "Net-(IC1-C)") (class "Default")
      (node (ref "D1") (pin "A") (pinfunction "A_A") (pintype "passive"))
      (node (ref "IC1") (pin "2") (pinfunction "C_2") (pintype "passive"))
      (node (ref "J3") (pin "TIP") (pinfunction "TIP_TIP") (pintype "bidirectional"))
    )
    (net (code "36") (name "Net-(J1-PadRING1)") (class "Default")
      (node (ref "J1") (pin "RING1") (pinfunction "RING1_RING1") (pintype "bidirectional"))
      (node (ref "R23") (pin "2") (pinfunction "2_2") (pintype "passive"))
    )
    (net (code "37") (name "Net-(J1-PadTIP)") (class "Default")
      (node (ref "J1") (pin "TIP") (pinfunction "TIP_TIP") (pintype "bidirectional"))
      (node (ref "R24") (pin "2") (pinfunction "2_2") (pintype "passive"))
    )
    (net (code "38") (name "Net-(J3-PadRING1)") (class "Default")
      (node (ref "J3") (pin "RING1") (pinfunction "RING1_RING1") (pintype "bidirectional"))
      (node (ref "R26") (pin "2") (pinfunction "2_2") (pintype "passive"))
    )
    (net (code "39") (name "Net-(LED1-DO)") (class "Default")
      (node (ref "LED1") (pin "2-DOUT") (pinfunction "DO_2-DOUT") (pintype "output"))
      (node (ref "LED2") (pin "4-DIN") (pinfunction "DI_4-DIN") (pintype "input"))
    )
    (net (code "40") (name "Net-(LED2-DO)") (class "Default")
      (node (ref "LED2") (pin "2-DOUT") (pinfunction "DO_2-DOUT") (pintype "output"))
      (node (ref "LED3") (pin "4-DIN") (pinfunction "DI_4-DIN") (pintype "input"))
    )
    (net (code "41") (name "Net-(LED3-DO)") (class "Default")
      (node (ref "LED3") (pin "2-DOUT") (pinfunction "DO_2-DOUT") (pintype "output"))
      (node (ref "LED4") (pin "4-DIN") (pinfunction "DI_4-DIN") (pintype "input"))
    )
    (net (code "42") (name "Net-(LED4-DO)") (class "Default")
      (node (ref "LED4") (pin "2-DOUT") (pinfunction "DO_2-DOUT") (pintype "output"))
      (node (ref "LED5") (pin "4-DIN") (pinfunction "DI_4-DIN") (pintype "input"))
    )
    (net (code "43") (name "Net-(LED5-DO)") (class "Default")
      (node (ref "LED5") (pin "2-DOUT") (pinfunction "DO_2-DOUT") (pintype "output"))
      (node (ref "LED6") (pin "4-DIN") (pinfunction "DI_4-DIN") (pintype "input"))
    )
    (net (code "44") (name "Net-(LED6-DO)") (class "Default")
      (node (ref "LED6") (pin "2-DOUT") (pinfunction "DO_2-DOUT") (pintype "output"))
      (node (ref "LED7") (pin "4-DIN") (pinfunction "DI_4-DIN") (pintype "input"))
    )
    (net (code "45") (name "Net-(LED7-DO)") (class "Default")
      (node (ref "LED7") (pin "2-DOUT") (pinfunction "DO_2-DOUT") (pintype "output"))
      (node (ref "LED8") (pin "4-DIN") (pinfunction "DI_4-DIN") (pintype "input"))
    )
    (net (code "46") (name "Net-(LED8-DO)") (class "Default")
      (node (ref "LED8") (pin "2-DOUT") (pinfunction "DO_2-DOUT") (pintype "output"))
      (node (ref "LED9") (pin "4-DIN") (pinfunction "DI_4-DIN") (pintype "input"))
    )
    (net (code "47") (name "Net-(LED10-DI)") (class "Default")
      (node (ref "LED10") (pin "4-DIN") (pinfunction "DI_4-DIN") (pintype "input"))
      (node (ref "LED9") (pin "2-DOUT") (pinfunction "DO_2-DOUT") (pintype "output"))
    )
    (net (code "48") (name "Net-(LED10-DO)") (class "Default")
      (node (ref "LED10") (pin "2-DOUT") (pinfunction "DO_2-DOUT") (pintype "output"))
      (node (ref "LED11") (pin "4-DIN") (pinfunction "DI_4-DIN") (pintype "input"))
    )
    (net (code "49") (name "Net-(LED11-DO)") (class "Default")
      (node (ref "LED11") (pin "2-DOUT") (pinfunction "DO_2-DOUT") (pintype "output"))
      (node (ref "LED12") (pin "4-DIN") (pinfunction "DI_4-DIN") (pintype "input"))
    )
    (net (code "50") (name "Net-(LED12-DO)") (class "Default")
      (node (ref "LED12") (pin "2-DOUT") (pinfunction "DO_2-DOUT") (pintype "output"))
      (node (ref "LED13") (pin "4-DIN") (pinfunction "DI_4-DIN") (pintype "input"))
    )
    (net (code "51") (name "Net-(LED13-DO)") (class "Default")
      (node (ref "LED13") (pin "2-DOUT") (pinfunction "DO_2-DOUT") (pintype "output"))
      (node (ref "LED14") (pin "4-DIN") (pinfunction "DI_4-DIN") (pintype "input"))
    )
    (net (code "52") (name "Net-(LED14-DO)") (class "Default")
      (node (ref "LED14") (pin "2-DOUT") (pinfunction "DO_2-DOUT") (pintype "output"))
      (node (ref "LED15") (pin "4-DIN") (pinfunction "DI_4-DIN") (pintype "input"))
    )
    (net (code "53") (name "Net-(LED15-DO)") (class "Default")
      (node (ref "LED15") (pin "2-DOUT") (pinfunction "DO_2-DOUT") (pintype "output"))
      (node (ref "LED16") (pin "4-DIN") (pinfunction "DI_4-DIN") (pintype "input"))
    )
    (net (code "54") (name "Net-(LED16-DO)") (class "Default")
      (node (ref "LED16") (pin "2-DOUT") (pinfunction "DO_2-DOUT") (pintype "output"))
      (node (ref "LED17") (pin "4-DIN") (pinfunction "DI_4-DIN") (pintype "input"))
    )
    (net (code "55") (name "Net-(LED17-DO)") (class "Default")
      (node (ref "LED17") (pin "2-DOUT") (pinfunction "DO_2-DOUT") (pintype "output"))
      (node (ref "LED18") (pin "4-DIN") (pinfunction "DI_4-DIN") (pintype "input"))
    )
    (net (code "56") (name "Net-(LED18-DO)") (class "Default")
      (node (ref "LED18") (pin "2-DOUT") (pinfunction "DO_2-DOUT") (pintype "output"))
      (node (ref "LED19") (pin "4-DIN") (pinfunction "DI_4-DIN") (pintype "input"))
    )
    (net (code "57") (name "Net-(LED19-DO)") (class "Default")
      (node (ref "LED19") (pin "2-DOUT") (pinfunction "DO_2-DOUT") (pintype "output"))
      (node (ref "LED20") (pin "4-DIN") (pinfunction "DI_4-DIN") (pintype "input"))
    )
    (net (code "58") (name "unconnected-(J1-PadRING2)") (class "Default")
      (node (ref "J1") (pin "RING2") (pinfunction "RING2_RING2") (pintype "bidirectional"))
    )
    (net (code "59") (name "unconnected-(J3-PadRING2)") (class "Default")
      (node (ref "J3") (pin "RING2") (pinfunction "RING2_RING2") (pintype "bidirectional"))
    )
    (net (code "60") (name "unconnected-(LED20-DO-Pad2-DOUT)") (class "Default")
      (node (ref "LED20") (pin "2-DOUT") (pinfunction "DO_2-DOUT") (pintype "output"))
    )
    (net (code "61") (name "unconnected-(U1-3V3_EN-PadP$37)") (class "Default")
      (node (ref "U1") (pin "P$37") (pinfunction "3V3_EN_P$37") (pintype "input"))
    )
    (net (code "62") (name "unconnected-(U1-ADC_REF-PadP$35)") (class "Default")
      (node (ref "U1") (pin "P$35") (pinfunction "ADC_REF_P$35") (pintype "input"))
    )
    (net (code "63") (name "unconnected-(U1-RUN-PadP$30)") (class "Default")
      (node (ref "U1") (pin "P$30") (pinfunction "RUN_P$30") (pintype "input"))
    )
    (net (code "64") (name "unconnected-(U1-SWCLK-PadP$41)") (class "Default")
      (node (ref "U1") (pin "P$41") (pinfunction "SWCLK_P$41") (pintype "input"))
    )
    (net (code "65") (name "unconnected-(U1-SWDIO-PadP$43)") (class "Default")
      (node (ref "U1") (pin "P$43") (pinfunction "SWDIO_P$43") (pintype "bidirectional"))
    )
  )
)
